# lines.net
KiCad netlist of a schematic drawn in EAGLE
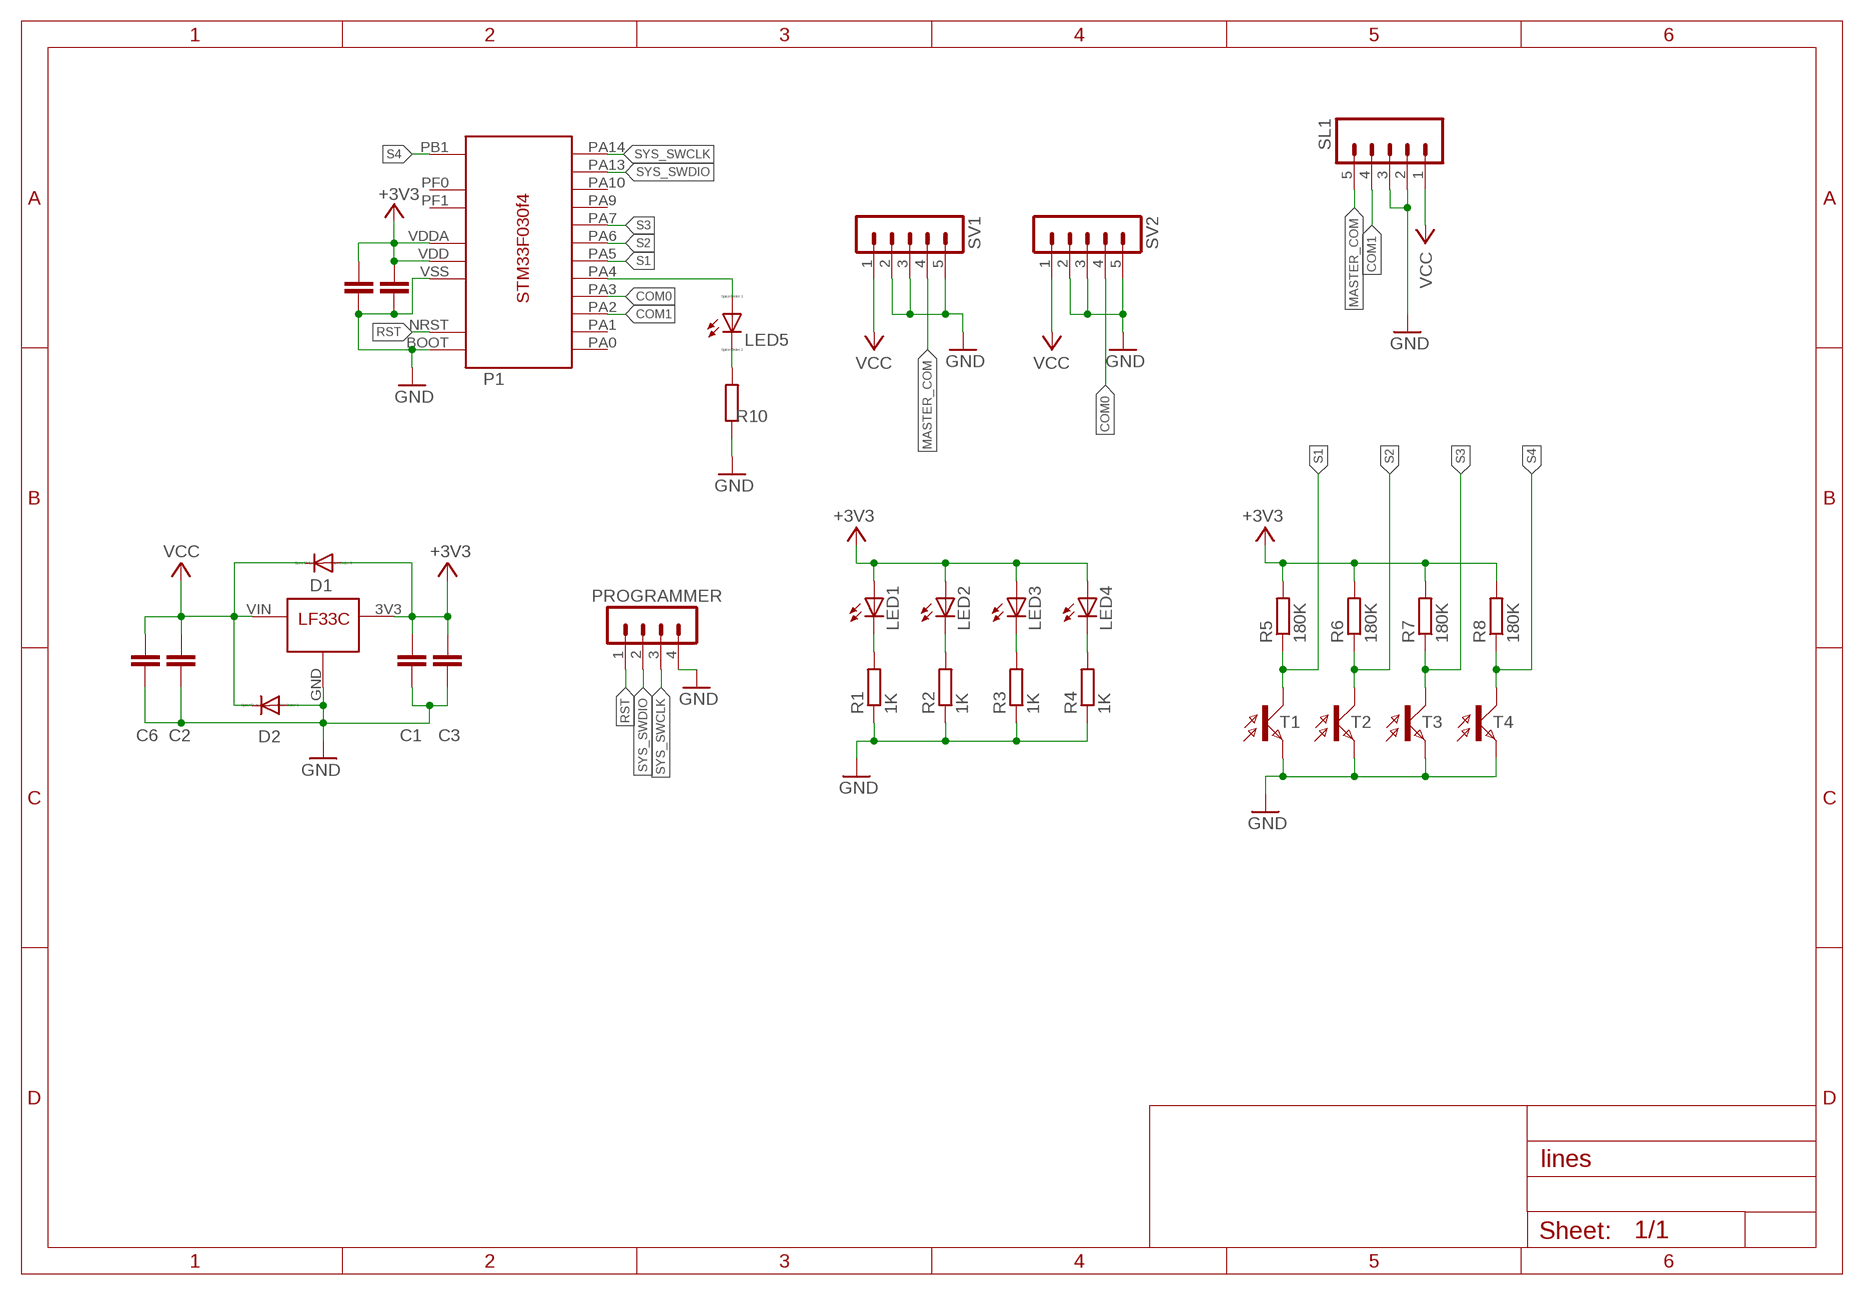
[diagram p0: schematic, sheet 1]

(export (version "E")
  (design (tool "Eeschema 10.0.6"))
  (components
    (comp (ref "C1")
      (value "100k")
      (footprint "eagle-import:C0603")
      (libsource (lib "eagle-import") (part "C-EUC0603"))
    )
    (comp (ref "C2")
      (value "100k")
      (footprint "eagle-import:C0603")
      (libsource (lib "eagle-import") (part "C-EUC0603"))
    )
    (comp (ref "C3")
      (value "10u")
      (footprint "eagle-import:C1206")
      (libsource (lib "eagle-import") (part "C-EUC1206"))
    )
    (comp (ref "C4")
      (value "100K")
      (footprint "eagle-import:C0603")
      (libsource (lib "eagle-import") (part "C-EUC0603"))
    )
    (comp (ref "C5")
      (value "100K")
      (footprint "eagle-import:C0603")
      (libsource (lib "eagle-import") (part "C-EUC0603"))
    )
    (comp (ref "C6")
      (value "10u")
      (footprint "eagle-import:C1206")
      (libsource (lib "eagle-import") (part "C-EUC1206"))
    )
    (comp (ref "D1")
      (value "DIODE-MINIMELF")
      (footprint "eagle-import:MINIMELF")
      (libsource (lib "eagle-import") (part "DIODE-MINIMELF"))
    )
    (comp (ref "D2")
      (value "DIODE-MINIMELF")
      (footprint "eagle-import:MINIMELF")
      (libsource (lib "eagle-import") (part "DIODE-MINIMELF"))
    )
    (comp (ref "LED1")
      (value "LED5MM")
      (footprint "eagle-import:LED5MM")
      (libsource (lib "eagle-import") (part "LED5MM"))
    )
    (comp (ref "LED2")
      (value "LED5MM")
      (footprint "eagle-import:LED5MM")
      (libsource (lib "eagle-import") (part "LED5MM"))
    )
    (comp (ref "LED3")
      (value "LED5MM")
      (footprint "eagle-import:LED5MM")
      (libsource (lib "eagle-import") (part "LED5MM"))
    )
    (comp (ref "LED4")
      (value "LED5MM")
      (footprint "eagle-import:LED5MM")
      (libsource (lib "eagle-import") (part "LED5MM"))
    )
    (comp (ref "LED5")
      (value "LED_E")
      (footprint "eagle-import:LED_1206")
      (libsource (lib "eagle-import") (part "LED_E"))
    )
    (comp (ref "P1")
      (value "STM32F030F4")
      (footprint "eagle-import:STM32F030F4")
      (libsource (lib "eagle-import") (part "STM32F030F4"))
    )
    (comp (ref "PROGRAMMER")
      (value "MA04-1")
      (footprint "eagle-import:MA04-1")
      (libsource (lib "eagle-import") (part "MA04-1"))
    )
    (comp (ref "R1")
      (value "1K")
      (footprint "eagle-import:R0603")
      (libsource (lib "eagle-import") (part "R-EU_R0603"))
    )
    (comp (ref "R2")
      (value "1K")
      (footprint "eagle-import:R0603")
      (libsource (lib "eagle-import") (part "R-EU_R0603"))
    )
    (comp (ref "R3")
      (value "1K")
      (footprint "eagle-import:R0603")
      (libsource (lib "eagle-import") (part "R-EU_R0603"))
    )
    (comp (ref "R4")
      (value "1K")
      (footprint "eagle-import:R0603")
      (libsource (lib "eagle-import") (part "R-EU_R0603"))
    )
    (comp (ref "R5")
      (value "180K")
      (footprint "eagle-import:R0603")
      (libsource (lib "eagle-import") (part "R-EU_R0603"))
    )
    (comp (ref "R6")
      (value "180K")
      (footprint "eagle-import:R0603")
      (libsource (lib "eagle-import") (part "R-EU_R0603"))
    )
    (comp (ref "R7")
      (value "180K")
      (footprint "eagle-import:R0603")
      (libsource (lib "eagle-import") (part "R-EU_R0603"))
    )
    (comp (ref "R8")
      (value "180K")
      (footprint "eagle-import:R0603")
      (libsource (lib "eagle-import") (part "R-EU_R0603"))
    )
    (comp (ref "R10")
      (value "R-EU_R0603")
      (footprint "eagle-import:R0603")
      (libsource (lib "eagle-import") (part "R-EU_R0603"))
    )
    (comp (ref "SL1")
      (value "M05")
      (footprint "eagle-import:05P")
      (libsource (lib "eagle-import") (part "M05"))
    )
    (comp (ref "SV1")
      (value "MA05-1")
      (footprint "eagle-import:MA05-1")
      (libsource (lib "eagle-import") (part "MA05-1"))
    )
    (comp (ref "SV2")
      (value "MA05-1")
      (footprint "eagle-import:MA05-1")
      (libsource (lib "eagle-import") (part "MA05-1"))
    )
    (comp (ref "T1")
      (value "BPX81")
      (footprint "eagle-import:BPX81")
      (libsource (lib "eagle-import") (part "BPX81"))
    )
    (comp (ref "T2")
      (value "BPX81")
      (footprint "eagle-import:BPX81")
      (libsource (lib "eagle-import") (part "BPX81"))
    )
    (comp (ref "T3")
      (value "BPX81")
      (footprint "eagle-import:BPX81")
      (libsource (lib "eagle-import") (part "BPX81"))
    )
    (comp (ref "T4")
      (value "BPX81")
      (footprint "eagle-import:BPX81")
      (libsource (lib "eagle-import") (part "BPX81"))
    )
    (comp (ref "U$1")
      (value "LF33C")
      (footprint "eagle-import:LF33C")
      (libsource (lib "eagle-import") (part "LF33C"))
    )
  )
  (nets
    (net (code "1") (name "+3V3") (class "Default")
      (node (ref "C1") (pin "1") (pinfunction "1_1") (pintype "passive"))
      (node (ref "C3") (pin "1") (pinfunction "1_1") (pintype "passive"))
      (node (ref "C4") (pin "1") (pinfunction "1_1") (pintype "passive"))
      (node (ref "C5") (pin "1") (pinfunction "1_1") (pintype "passive"))
      (node (ref "D1") (pin "A") (pinfunction "A_A") (pintype "passive"))
      (node (ref "LED1") (pin "A") (pinfunction "A_A") (pintype "passive"))
      (node (ref "LED2") (pin "A") (pinfunction "A_A") (pintype "passive"))
      (node (ref "LED3") (pin "A") (pinfunction "A_A") (pintype "passive"))
      (node (ref "LED4") (pin "A") (pinfunction "A_A") (pintype "passive"))
      (node (ref "P1") (pin "VDD") (pinfunction "VDD_VDD") (pintype "bidirectional"))
      (node (ref "P1") (pin "VDDA") (pinfunction "VDDA_VDDA") (pintype "bidirectional"))
      (node (ref "R5") (pin "2") (pinfunction "2_2") (pintype "passive"))
      (node (ref "R6") (pin "2") (pinfunction "2_2") (pintype "passive"))
      (node (ref "R7") (pin "2") (pinfunction "2_2") (pintype "passive"))
      (node (ref "R8") (pin "2") (pinfunction "2_2") (pintype "passive"))
      (node (ref "U$1") (pin "3V3") (pinfunction "3V3_3V3") (pintype "bidirectional"))
    )
    (net (code "2") (name "COM0") (class "Default")
      (node (ref "P1") (pin "PA3") (pinfunction "PA3_PA3") (pintype "bidirectional"))
      (node (ref "SV2") (pin "4") (pinfunction "4_4") (pintype "passive"))
    )
    (net (code "3") (name "COM1") (class "Default")
      (node (ref "P1") (pin "PA2") (pinfunction "PA2_PA2") (pintype "bidirectional"))
      (node (ref "SL1") (pin "4") (pinfunction "4_4") (pintype "passive"))
    )
    (net (code "4") (name "GND") (class "Default")
      (node (ref "C1") (pin "2") (pinfunction "2_2") (pintype "passive"))
      (node (ref "C2") (pin "2") (pinfunction "2_2") (pintype "passive"))
      (node (ref "C3") (pin "2") (pinfunction "2_2") (pintype "passive"))
      (node (ref "C4") (pin "2") (pinfunction "2_2") (pintype "passive"))
      (node (ref "C5") (pin "2") (pinfunction "2_2") (pintype "passive"))
      (node (ref "C6") (pin "2") (pinfunction "2_2") (pintype "passive"))
      (node (ref "D2") (pin "A") (pinfunction "A_A") (pintype "passive"))
      (node (ref "P1") (pin "BOOT") (pinfunction "BOOT_BOOT") (pintype "bidirectional"))
      (node (ref "P1") (pin "VSS") (pinfunction "VSS_VSS") (pintype "bidirectional"))
      (node (ref "PROGRAMMER") (pin "4") (pinfunction "4_4") (pintype "passive"))
      (node (ref "R1") (pin "1") (pinfunction "1_1") (pintype "passive"))
      (node (ref "R10") (pin "1") (pinfunction "1_1") (pintype "passive"))
      (node (ref "R2") (pin "1") (pinfunction "1_1") (pintype "passive"))
      (node (ref "R3") (pin "1") (pinfunction "1_1") (pintype "passive"))
      (node (ref "R4") (pin "1") (pinfunction "1_1") (pintype "passive"))
      (node (ref "SL1") (pin "2") (pinfunction "2_2") (pintype "passive"))
      (node (ref "SL1") (pin "3") (pinfunction "3_3") (pintype "passive"))
      (node (ref "SV1") (pin "2") (pinfunction "2_2") (pintype "passive"))
      (node (ref "SV1") (pin "3") (pinfunction "3_3") (pintype "passive"))
      (node (ref "SV1") (pin "5") (pinfunction "5_5") (pintype "passive"))
      (node (ref "SV2") (pin "2") (pinfunction "2_2") (pintype "passive"))
      (node (ref "SV2") (pin "3") (pinfunction "3_3") (pintype "passive"))
      (node (ref "SV2") (pin "5") (pinfunction "5_5") (pintype "passive"))
      (node (ref "T1") (pin "E") (pinfunction "E_E") (pintype "passive"))
      (node (ref "T2") (pin "E") (pinfunction "E_E") (pintype "passive"))
      (node (ref "T3") (pin "E") (pinfunction "E_E") (pintype "passive"))
      (node (ref "T4") (pin "E") (pinfunction "E_E") (pintype "passive"))
      (node (ref "U$1") (pin "GND") (pinfunction "GND_GND") (pintype "bidirectional"))
    )
    (net (code "5") (name "MASTER_COM") (class "Default")
      (node (ref "SL1") (pin "5") (pinfunction "5_5") (pintype "passive"))
      (node (ref "SV1") (pin "4") (pinfunction "4_4") (pintype "passive"))
    )
    (net (code "6") (name "Net-(LED1-C)") (class "Default")
      (node (ref "LED1") (pin "K") (pinfunction "C_K") (pintype "passive"))
      (node (ref "R1") (pin "2") (pinfunction "2_2") (pintype "passive"))
    )
    (net (code "7") (name "Net-(LED2-C)") (class "Default")
      (node (ref "LED2") (pin "K") (pinfunction "C_K") (pintype "passive"))
      (node (ref "R2") (pin "2") (pinfunction "2_2") (pintype "passive"))
    )
    (net (code "8") (name "Net-(LED3-C)") (class "Default")
      (node (ref "LED3") (pin "K") (pinfunction "C_K") (pintype "passive"))
      (node (ref "R3") (pin "2") (pinfunction "2_2") (pintype "passive"))
    )
    (net (code "9") (name "Net-(LED4-C)") (class "Default")
      (node (ref "LED4") (pin "K") (pinfunction "C_K") (pintype "passive"))
      (node (ref "R4") (pin "2") (pinfunction "2_2") (pintype "passive"))
    )
    (net (code "10") (name "Net-(LED5-PadA)") (class "Default")
      (node (ref "LED5") (pin "A") (pinfunction "A_A") (pintype "passive"))
      (node (ref "P1") (pin "PA4") (pinfunction "PA4_PA4") (pintype "bidirectional"))
    )
    (net (code "11") (name "Net-(LED5-PadC)") (class "Default")
      (node (ref "LED5") (pin "C") (pinfunction "C_C") (pintype "passive"))
      (node (ref "R10") (pin "2") (pinfunction "2_2") (pintype "passive"))
    )
    (net (code "12") (name "RST") (class "Default")
      (node (ref "P1") (pin "NRST") (pinfunction "NRST_NRST") (pintype "bidirectional"))
      (node (ref "PROGRAMMER") (pin "1") (pinfunction "1_1") (pintype "passive"))
    )
    (net (code "13") (name "S1") (class "Default")
      (node (ref "P1") (pin "PA5") (pinfunction "PA5_PA5") (pintype "bidirectional"))
      (node (ref "R5") (pin "1") (pinfunction "1_1") (pintype "passive"))
      (node (ref "T1") (pin "C") (pinfunction "C_C") (pintype "passive"))
    )
    (net (code "14") (name "S2") (class "Default")
      (node (ref "P1") (pin "PA6") (pinfunction "PA6_PA6") (pintype "bidirectional"))
      (node (ref "R6") (pin "1") (pinfunction "1_1") (pintype "passive"))
      (node (ref "T2") (pin "C") (pinfunction "C_C") (pintype "passive"))
    )
    (net (code "15") (name "S3") (class "Default")
      (node (ref "P1") (pin "PA7") (pinfunction "PA7_PA7") (pintype "bidirectional"))
      (node (ref "R7") (pin "1") (pinfunction "1_1") (pintype "passive"))
      (node (ref "T3") (pin "C") (pinfunction "C_C") (pintype "passive"))
    )
    (net (code "16") (name "S4") (class "Default")
      (node (ref "P1") (pin "PB1") (pinfunction "PB1_PB1") (pintype "bidirectional"))
      (node (ref "R8") (pin "1") (pinfunction "1_1") (pintype "passive"))
      (node (ref "T4") (pin "C") (pinfunction "C_C") (pintype "passive"))
    )
    (net (code "17") (name "SYS_SWCLK") (class "Default")
      (node (ref "P1") (pin "PA14") (pinfunction "PA14_PA14") (pintype "bidirectional"))
      (node (ref "PROGRAMMER") (pin "3") (pinfunction "3_3") (pintype "passive"))
    )
    (net (code "18") (name "SYS_SWDIO") (class "Default")
      (node (ref "P1") (pin "PA13") (pinfunction "PA13_PA13") (pintype "bidirectional"))
      (node (ref "PROGRAMMER") (pin "2") (pinfunction "2_2") (pintype "passive"))
    )
    (net (code "19") (name "VCC") (class "Default")
      (node (ref "C2") (pin "1") (pinfunction "1_1") (pintype "passive"))
      (node (ref "C6") (pin "1") (pinfunction "1_1") (pintype "passive"))
      (node (ref "D1") (pin "C") (pinfunction "C_C") (pintype "passive"))
      (node (ref "D2") (pin "C") (pinfunction "C_C") (pintype "passive"))
      (node (ref "SL1") (pin "1") (pinfunction "1_1") (pintype "passive"))
      (node (ref "SV1") (pin "1") (pinfunction "1_1") (pintype "passive"))
      (node (ref "SV2") (pin "1") (pinfunction "1_1") (pintype "passive"))
      (node (ref "U$1") (pin "VIN") (pinfunction "VIN_VIN") (pintype "bidirectional"))
    )
    (net (code "20") (name "unconnected-(P1-PadPA0)") (class "Default")
      (node (ref "P1") (pin "PA0") (pinfunction "PA0_PA0") (pintype "bidirectional"))
    )
    (net (code "21") (name "unconnected-(P1-PadPA1)") (class "Default")
      (node (ref "P1") (pin "PA1") (pinfunction "PA1_PA1") (pintype "bidirectional"))
    )
    (net (code "22") (name "unconnected-(P1-PadPA9)") (class "Default")
      (node (ref "P1") (pin "PA9") (pinfunction "PA9_PA9") (pintype "bidirectional"))
    )
    (net (code "23") (name "unconnected-(P1-PadPA10)") (class "Default")
      (node (ref "P1") (pin "PA10") (pinfunction "PA10_PA10") (pintype "bidirectional"))
    )
    (net (code "24") (name "unconnected-(P1-PadPF0)") (class "Default")
      (node (ref "P1") (pin "PF0") (pinfunction "PF0_PF0") (pintype "bidirectional"))
    )
    (net (code "25") (name "unconnected-(P1-PadPF1)") (class "Default")
      (node (ref "P1") (pin "PF1") (pinfunction "PF1_PF1") (pintype "bidirectional"))
    )
  )
)
